# MicroCutter.net
KiCad netlist of a schematic drawn in EAGLE
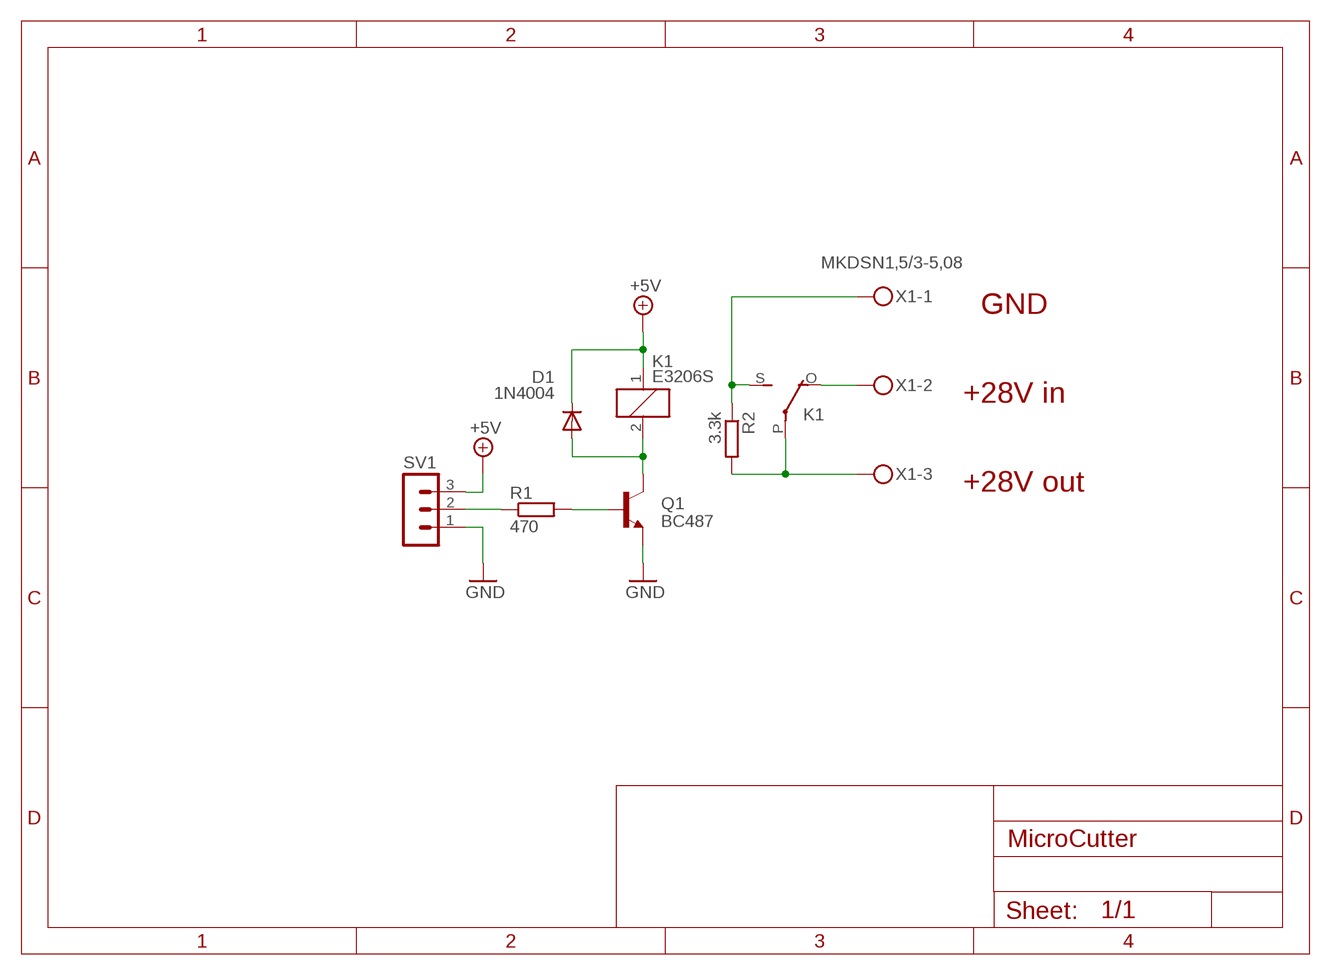
[diagram p0: schematic, sheet 1]

(export (version "E")
  (design (tool "Eeschema 10.0.6"))
  (components
    (comp (ref "D1")
      (value "1N4004")
      (footprint "eagle-import:DO41-10")
      (libsource (lib "eagle-import") (part "1N4004"))
    )
    (comp (ref "K1")
      (value "E3206S")
      (footprint "eagle-import:E3206S")
      (libsource (lib "eagle-import") (part "E3206S"))
    )
    (comp (ref "Q1")
      (value "BC487")
      (footprint "eagle-import:TO92-EBC")
      (libsource (lib "eagle-import") (part "BC487"))
    )
    (comp (ref "R1")
      (value "470")
      (footprint "eagle-import:0309_12")
      (libsource (lib "eagle-import") (part "R-EU_0309/12"))
    )
    (comp (ref "R2")
      (value "3.3k")
      (footprint "eagle-import:0309_12")
      (libsource (lib "eagle-import") (part "R-EU_0309/12"))
    )
    (comp (ref "SV1")
      (value "MA03-1")
      (footprint "eagle-import:MA03-1")
      (libsource (lib "eagle-import") (part "MA03-1"))
    )
    (comp (ref "X1")
      (value "MKDSN1,5/3-5,08")
      (footprint "eagle-import:MKDSN1,5_3-5,08")
      (libsource (lib "eagle-import") (part "MKDSN1,5/3-5,08"))
    )
  )
  (nets
    (net (code "1") (name "+5V") (class "Default")
      (node (ref "D1") (pin "C") (pinfunction "C_C") (pintype "passive"))
      (node (ref "K1") (pin "1") (pinfunction "1_1") (pintype "passive"))
      (node (ref "SV1") (pin "3") (pinfunction "3_3") (pintype "passive"))
    )
    (net (code "2") (name "GND") (class "Default")
      (node (ref "Q1") (pin "E") (pinfunction "E_E") (pintype "passive"))
      (node (ref "SV1") (pin "1") (pinfunction "1_1") (pintype "passive"))
    )
    (net (code "3") (name "Net-(D1-PadA)") (class "Default")
      (node (ref "D1") (pin "A") (pinfunction "A_A") (pintype "passive"))
      (node (ref "K1") (pin "2") (pinfunction "2_2") (pintype "passive"))
      (node (ref "Q1") (pin "C") (pinfunction "C_C") (pintype "passive"))
    )
    (net (code "4") (name "Net-(Q1-PadB)") (class "Default")
      (node (ref "Q1") (pin "B") (pinfunction "B_B") (pintype "passive"))
      (node (ref "R1") (pin "2") (pinfunction "2_2") (pintype "passive"))
    )
    (net (code "5") (name "Net-(R1-Pad1)") (class "Default")
      (node (ref "R1") (pin "1") (pinfunction "1_1") (pintype "passive"))
      (node (ref "SV1") (pin "2") (pinfunction "2_2") (pintype "passive"))
    )
    (net (code "6") (name "Net-(X1A-KL)") (class "Default")
      (node (ref "K1") (pin "S") (pinfunction "S_S") (pintype "passive"))
      (node (ref "R2") (pin "1") (pinfunction "1_1") (pintype "passive"))
      (node (ref "X1") (pin "1") (pinfunction "KL_1") (pintype "passive"))
    )
    (net (code "7") (name "Net-(X1B-KL)") (class "Default")
      (node (ref "K1") (pin "O") (pinfunction "O_O") (pintype "passive"))
      (node (ref "X1") (pin "2") (pinfunction "KL_2") (pintype "passive"))
    )
    (net (code "8") (name "Net-(X1C-KL)") (class "Default")
      (node (ref "K1") (pin "P") (pinfunction "P_P") (pintype "passive"))
      (node (ref "R2") (pin "2") (pinfunction "2_2") (pintype "passive"))
      (node (ref "X1") (pin "3") (pinfunction "KL_3") (pintype "passive"))
    )
  )
)
